# Round_Rev3.net
KiCad netlist of a schematic drawn in EAGLE
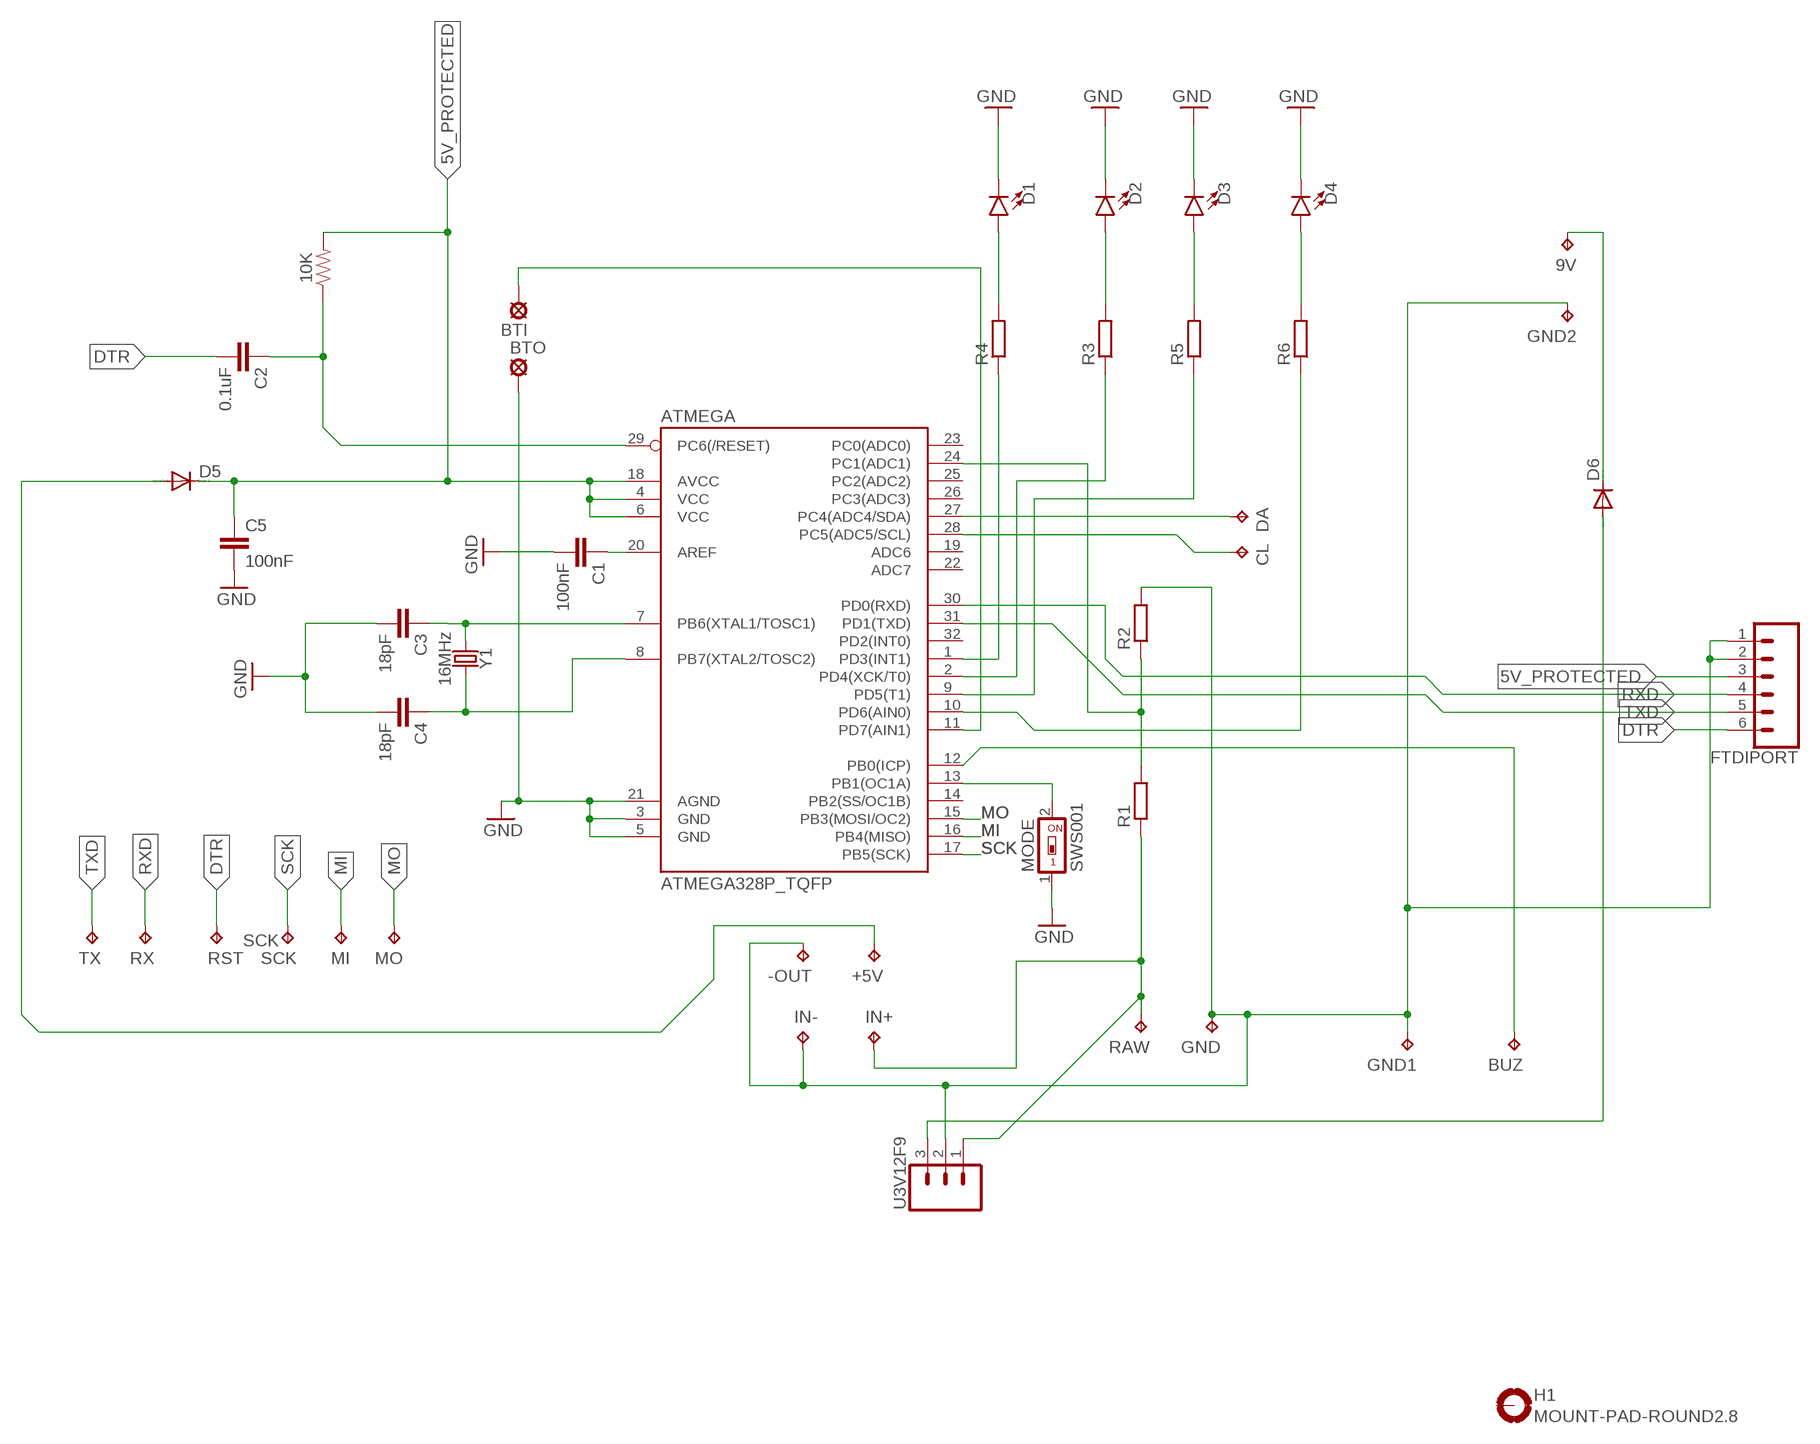
[diagram p0: schematic, sheet 1]

(export (version "E")
  (design (tool "Eeschema 10.0.6"))
  (components
    (comp (ref "+5V")
      (value "TPTP20SQ")
      (footprint "eagle-import:TP20SQ")
      (libsource (lib "eagle-import") (part "TPTP20SQ"))
    )
    (comp (ref "-OUT")
      (value "TPTP20SQ")
      (footprint "eagle-import:TP20SQ")
      (libsource (lib "eagle-import") (part "TPTP20SQ"))
    )
    (comp (ref "9V")
      (value "TPB2,54")
      (footprint "eagle-import:B2,54")
      (libsource (lib "eagle-import") (part "TPB2,54"))
    )
    (comp (ref "10K")
      (value "0.27OHM-0603-1/10W-1%")
      (footprint "eagle-import:0603")
      (libsource (lib "eagle-import") (part "0.27OHM-0603-1/10W-1%"))
    )
    (comp (ref "ATMEGA")
      (value "ATMEGA328P_TQFP")
      (footprint "eagle-import:TQFP32-08")
      (libsource (lib "eagle-import") (part "ATMEGA328P_TQFP"))
    )
    (comp (ref "BTI")
      (value "LSP10")
      (footprint "eagle-import:LSP10")
      (libsource (lib "eagle-import") (part "LSP10"))
    )
    (comp (ref "BTO")
      (value "LSP10")
      (footprint "eagle-import:LSP10")
      (libsource (lib "eagle-import") (part "LSP10"))
    )
    (comp (ref "BUZ")
      (value "TPB2,54")
      (footprint "eagle-import:B2,54")
      (libsource (lib "eagle-import") (part "TPB2,54"))
    )
    (comp (ref "C1")
      (value "100nF")
      (footprint "eagle-import:0603")
      (libsource (lib "eagle-import") (part "10NF-0603-50V-10%"))
    )
    (comp (ref "C2")
      (value "0.1uF")
      (footprint "eagle-import:0603")
      (libsource (lib "eagle-import") (part "10NF-0603-50V-10%"))
    )
    (comp (ref "C3")
      (value "18pF")
      (footprint "eagle-import:0603")
      (libsource (lib "eagle-import") (part "10NF-0603-50V-10%"))
    )
    (comp (ref "C4")
      (value "18pF")
      (footprint "eagle-import:0603")
      (libsource (lib "eagle-import") (part "10NF-0603-50V-10%"))
    )
    (comp (ref "C5")
      (value "100nF")
      (footprint "eagle-import:0603")
      (libsource (lib "eagle-import") (part "10NF-0603-50V-10%"))
    )
    (comp (ref "CL")
      (value "TPB1,27")
      (footprint "eagle-import:B1,27")
      (libsource (lib "eagle-import") (part "TPB1,27"))
    )
    (comp (ref "D1")
      (value "LED1206")
      (footprint "eagle-import:LED-1206")
      (libsource (lib "eagle-import") (part "LED1206"))
    )
    (comp (ref "D2")
      (value "LED1206")
      (footprint "eagle-import:LED-1206")
      (libsource (lib "eagle-import") (part "LED1206"))
    )
    (comp (ref "D3")
      (value "LED1206")
      (footprint "eagle-import:LED-1206")
      (libsource (lib "eagle-import") (part "LED1206"))
    )
    (comp (ref "D4")
      (value "LED1206")
      (footprint "eagle-import:LED-1206")
      (libsource (lib "eagle-import") (part "LED1206"))
    )
    (comp (ref "D5")
      (value "DIODE-SOD106A-R")
      (footprint "eagle-import:SOD106A-R")
      (libsource (lib "eagle-import") (part "DIODE-SOD106A-R"))
    )
    (comp (ref "D6")
      (value "DIODE-SOD106A-R")
      (footprint "eagle-import:SOD106A-R")
      (libsource (lib "eagle-import") (part "DIODE-SOD106A-R"))
    )
    (comp (ref "DA")
      (value "TPB1,27")
      (footprint "eagle-import:B1,27")
      (libsource (lib "eagle-import") (part "TPB1,27"))
    )
    (comp (ref "FTDIPORT")
      (value "CONN_06SMD-1MM")
      (footprint "eagle-import:1X06-1MM")
      (libsource (lib "eagle-import") (part "CONN_06SMD-1MM"))
    )
    (comp (ref "GND")
      (value "TPB2,54")
      (footprint "eagle-import:B2,54")
      (libsource (lib "eagle-import") (part "TPB2,54"))
    )
    (comp (ref "GND1")
      (value "TPB2,54")
      (footprint "eagle-import:B2,54")
      (libsource (lib "eagle-import") (part "TPB2,54"))
    )
    (comp (ref "GND2")
      (value "TPB2,54")
      (footprint "eagle-import:B2,54")
      (libsource (lib "eagle-import") (part "TPB2,54"))
    )
    (comp (ref "H1")
      (value "MOUNT-PAD-ROUND2.8")
      (footprint "eagle-import:2,8-PAD")
      (libsource (lib "eagle-import") (part "MOUNT-PAD-ROUND2.8"))
    )
    (comp (ref "IN+")
      (value "TPTP20SQ")
      (footprint "eagle-import:TP20SQ")
      (libsource (lib "eagle-import") (part "TPTP20SQ"))
    )
    (comp (ref "IN-")
      (value "TPTP20SQ")
      (footprint "eagle-import:TP20SQ")
      (libsource (lib "eagle-import") (part "TPTP20SQ"))
    )
    (comp (ref "MI")
      (value "TPB1,27")
      (footprint "eagle-import:B1,27")
      (libsource (lib "eagle-import") (part "TPB1,27"))
    )
    (comp (ref "MO")
      (value "TPB1,27")
      (footprint "eagle-import:B1,27")
      (libsource (lib "eagle-import") (part "TPB1,27"))
    )
    (comp (ref "MODE")
      (value "SWS001")
      (footprint "eagle-import:SMS-001")
      (libsource (lib "eagle-import") (part "SWS001"))
    )
    (comp (ref "R1")
      (value "R-EU_R1206")
      (footprint "eagle-import:R1206")
      (libsource (lib "eagle-import") (part "R-EU_R1206"))
    )
    (comp (ref "R2")
      (value "R-EU_R1206")
      (footprint "eagle-import:R1206")
      (libsource (lib "eagle-import") (part "R-EU_R1206"))
    )
    (comp (ref "R3")
      (value "R-EU_R1206")
      (footprint "eagle-import:R1206")
      (libsource (lib "eagle-import") (part "R-EU_R1206"))
    )
    (comp (ref "R4")
      (value "R-EU_R1206")
      (footprint "eagle-import:R1206")
      (libsource (lib "eagle-import") (part "R-EU_R1206"))
    )
    (comp (ref "R5")
      (value "R-EU_R1206")
      (footprint "eagle-import:R1206")
      (libsource (lib "eagle-import") (part "R-EU_R1206"))
    )
    (comp (ref "R6")
      (value "R-EU_R1206")
      (footprint "eagle-import:R1206")
      (libsource (lib "eagle-import") (part "R-EU_R1206"))
    )
    (comp (ref "RAW")
      (value "TPB2,54")
      (footprint "eagle-import:B2,54")
      (libsource (lib "eagle-import") (part "TPB2,54"))
    )
    (comp (ref "RST")
      (value "TPB1,27")
      (footprint "eagle-import:B1,27")
      (libsource (lib "eagle-import") (part "TPB1,27"))
    )
    (comp (ref "RX")
      (value "TPB1,27")
      (footprint "eagle-import:B1,27")
      (libsource (lib "eagle-import") (part "TPB1,27"))
    )
    (comp (ref "SCK")
      (value "TPB1,27")
      (footprint "eagle-import:B1,27")
      (fields (field (name "TP_SIGNAL_NAME") "SCK"))
      (libsource (lib "eagle-import") (part "TPB1,27"))
    )
    (comp (ref "TX")
      (value "TPB1,27")
      (footprint "eagle-import:B1,27")
      (libsource (lib "eagle-import") (part "TPB1,27"))
    )
    (comp (ref "U3V12F9")
      (value "CONN_03")
      (footprint "eagle-import:1X03")
      (libsource (lib "eagle-import") (part "CONN_03"))
    )
    (comp (ref "Y1")
      (value "16MHz")
      (footprint "eagle-import:CRYSTAL-SMD-5X3.2-2PAD")
      (libsource (lib "eagle-import") (part "CRYSTALSMD-5X3.2-2PAD"))
    )
  )
  (nets
    (net (code "1") (name "5V_PROTECTED") (class "Default")
      (node (ref "10K") (pin "2") (pinfunction "2_2") (pintype "passive"))
      (node (ref "ATMEGA") (pin "18") (pinfunction "AVCC_18") (pintype "bidirectional"))
      (node (ref "ATMEGA") (pin "4") (pinfunction "VCC_4") (pintype "bidirectional"))
      (node (ref "ATMEGA") (pin "6") (pinfunction "VCC_6") (pintype "bidirectional"))
      (node (ref "C5") (pin "1") (pinfunction "1_1") (pintype "passive"))
      (node (ref "D5") (pin "C") (pinfunction "C_C") (pintype "passive"))
      (node (ref "FTDIPORT") (pin "3") (pinfunction "3_3") (pintype "passive"))
    )
    (net (code "2") (name "DTR") (class "Default")
      (node (ref "C2") (pin "2") (pinfunction "2_2") (pintype "passive"))
      (node (ref "FTDIPORT") (pin "6") (pinfunction "6_6") (pintype "passive"))
      (node (ref "RST") (pin "TP") (pinfunction "TP_TP") (pintype "input"))
    )
    (net (code "3") (name "GND") (class "Default")
      (node (ref "-OUT") (pin "TP") (pinfunction "TP_TP") (pintype "input"))
      (node (ref "ATMEGA") (pin "21") (pinfunction "AGND_21") (pintype "bidirectional"))
      (node (ref "ATMEGA") (pin "3") (pinfunction "GND_3") (pintype "bidirectional"))
      (node (ref "ATMEGA") (pin "5") (pinfunction "GND_5") (pintype "bidirectional"))
      (node (ref "BTO") (pin "MP") (pinfunction "MP_MP") (pintype "passive"))
      (node (ref "C1") (pin "2") (pinfunction "2_2") (pintype "passive"))
      (node (ref "C3") (pin "2") (pinfunction "2_2") (pintype "passive"))
      (node (ref "C4") (pin "2") (pinfunction "2_2") (pintype "passive"))
      (node (ref "C5") (pin "2") (pinfunction "2_2") (pintype "passive"))
      (node (ref "D1") (pin "C") (pinfunction "C_C") (pintype "passive"))
      (node (ref "D2") (pin "C") (pinfunction "C_C") (pintype "passive"))
      (node (ref "D3") (pin "C") (pinfunction "C_C") (pintype "passive"))
      (node (ref "D4") (pin "C") (pinfunction "C_C") (pintype "passive"))
      (node (ref "FTDIPORT") (pin "1") (pinfunction "1_1") (pintype "passive"))
      (node (ref "FTDIPORT") (pin "2") (pinfunction "2_2") (pintype "passive"))
      (node (ref "GND") (pin "TP") (pinfunction "TP_TP") (pintype "input"))
      (node (ref "GND1") (pin "TP") (pinfunction "TP_TP") (pintype "input"))
      (node (ref "GND2") (pin "TP") (pinfunction "TP_TP") (pintype "input"))
      (node (ref "IN-") (pin "TP") (pinfunction "TP_TP") (pintype "input"))
      (node (ref "MODE") (pin "1") (pinfunction "1_1") (pintype "passive"))
      (node (ref "R2") (pin "2") (pinfunction "2_2") (pintype "passive"))
      (node (ref "U3V12F9") (pin "2") (pinfunction "2_2") (pintype "passive"))
    )
    (net (code "4") (name "MI") (class "Default")
      (node (ref "ATMEGA") (pin "16") (pinfunction "PB4(MISO)_16") (pintype "bidirectional"))
      (node (ref "MI") (pin "TP") (pinfunction "TP_TP") (pintype "input"))
    )
    (net (code "5") (name "MO") (class "Default")
      (node (ref "ATMEGA") (pin "15") (pinfunction "PB3(MOSI/OC2)_15") (pintype "bidirectional"))
      (node (ref "MO") (pin "TP") (pinfunction "TP_TP") (pintype "input"))
    )
    (net (code "6") (name "Net-(+5V-PadTP)") (class "Default")
      (node (ref "+5V") (pin "TP") (pinfunction "TP_TP") (pintype "input"))
      (node (ref "D5") (pin "A") (pinfunction "A_A") (pintype "passive"))
    )
    (net (code "7") (name "Net-(9V-PadTP)") (class "Default")
      (node (ref "9V") (pin "TP") (pinfunction "TP_TP") (pintype "input"))
      (node (ref "D6") (pin "C") (pinfunction "C_C") (pintype "passive"))
    )
    (net (code "8") (name "Net-(ATMEGA-AREF)") (class "Default")
      (node (ref "ATMEGA") (pin "20") (pinfunction "AREF_20") (pintype "bidirectional"))
      (node (ref "C1") (pin "1") (pinfunction "1_1") (pintype "passive"))
    )
    (net (code "9") (name "Net-(ATMEGA-PB0(ICP))") (class "Default")
      (node (ref "ATMEGA") (pin "12") (pinfunction "PB0(ICP)_12") (pintype "bidirectional"))
      (node (ref "BUZ") (pin "TP") (pinfunction "TP_TP") (pintype "input"))
    )
    (net (code "10") (name "Net-(ATMEGA-PB1(OC1A))") (class "Default")
      (node (ref "ATMEGA") (pin "13") (pinfunction "PB1(OC1A)_13") (pintype "bidirectional"))
      (node (ref "MODE") (pin "2") (pinfunction "2_2") (pintype "passive"))
    )
    (net (code "11") (name "Net-(ATMEGA-PB6(XTAL1{slash}TOSC1))") (class "Default")
      (node (ref "ATMEGA") (pin "7") (pinfunction "PB6(XTAL1/TOSC1)_7") (pintype "bidirectional"))
      (node (ref "C3") (pin "1") (pinfunction "1_1") (pintype "passive"))
      (node (ref "Y1") (pin "P$1") (pinfunction "1_P$1") (pintype "passive"))
    )
    (net (code "12") (name "Net-(ATMEGA-PB7(XTAL2{slash}TOSC2))") (class "Default")
      (node (ref "ATMEGA") (pin "8") (pinfunction "PB7(XTAL2/TOSC2)_8") (pintype "bidirectional"))
      (node (ref "C4") (pin "1") (pinfunction "1_1") (pintype "passive"))
      (node (ref "Y1") (pin "P$2") (pinfunction "2_P$2") (pintype "passive"))
    )
    (net (code "13") (name "Net-(ATMEGA-PC1(ADC1))") (class "Default")
      (node (ref "ATMEGA") (pin "24") (pinfunction "PC1(ADC1)_24") (pintype "bidirectional"))
      (node (ref "R1") (pin "2") (pinfunction "2_2") (pintype "passive"))
      (node (ref "R2") (pin "1") (pinfunction "1_1") (pintype "passive"))
    )
    (net (code "14") (name "Net-(ATMEGA-PC4(ADC4{slash}SDA))") (class "Default")
      (node (ref "ATMEGA") (pin "27") (pinfunction "PC4(ADC4/SDA)_27") (pintype "bidirectional"))
      (node (ref "DA") (pin "TP") (pinfunction "TP_TP") (pintype "input"))
    )
    (net (code "15") (name "Net-(ATMEGA-PC5(ADC5{slash}SCL))") (class "Default")
      (node (ref "ATMEGA") (pin "28") (pinfunction "PC5(ADC5/SCL)_28") (pintype "bidirectional"))
      (node (ref "CL") (pin "TP") (pinfunction "TP_TP") (pintype "input"))
    )
    (net (code "16") (name "Net-(ATMEGA-PC6({slash}RESET))") (class "Default")
      (node (ref "10K") (pin "1") (pinfunction "1_1") (pintype "passive"))
      (node (ref "ATMEGA") (pin "29") (pinfunction "PC6(/RESET)_29") (pintype "bidirectional"))
      (node (ref "C2") (pin "1") (pinfunction "1_1") (pintype "passive"))
    )
    (net (code "17") (name "Net-(ATMEGA-PD3(INT1))") (class "Default")
      (node (ref "ATMEGA") (pin "1") (pinfunction "PD3(INT1)_1") (pintype "bidirectional"))
      (node (ref "R4") (pin "1") (pinfunction "1_1") (pintype "passive"))
    )
    (net (code "18") (name "Net-(ATMEGA-PD4(XCK{slash}T0))") (class "Default")
      (node (ref "ATMEGA") (pin "2") (pinfunction "PD4(XCK/T0)_2") (pintype "bidirectional"))
      (node (ref "R3") (pin "1") (pinfunction "1_1") (pintype "passive"))
    )
    (net (code "19") (name "Net-(ATMEGA-PD5(T1))") (class "Default")
      (node (ref "ATMEGA") (pin "9") (pinfunction "PD5(T1)_9") (pintype "bidirectional"))
      (node (ref "R5") (pin "1") (pinfunction "1_1") (pintype "passive"))
    )
    (net (code "20") (name "Net-(ATMEGA-PD6(AIN0))") (class "Default")
      (node (ref "ATMEGA") (pin "10") (pinfunction "PD6(AIN0)_10") (pintype "bidirectional"))
      (node (ref "R6") (pin "1") (pinfunction "1_1") (pintype "passive"))
    )
    (net (code "21") (name "Net-(ATMEGA-PD7(AIN1))") (class "Default")
      (node (ref "ATMEGA") (pin "11") (pinfunction "PD7(AIN1)_11") (pintype "bidirectional"))
      (node (ref "BTI") (pin "MP") (pinfunction "MP_MP") (pintype "passive"))
    )
    (net (code "22") (name "Net-(D1-PadA)") (class "Default")
      (node (ref "D1") (pin "A") (pinfunction "A_A") (pintype "passive"))
      (node (ref "R4") (pin "2") (pinfunction "2_2") (pintype "passive"))
    )
    (net (code "23") (name "Net-(D2-PadA)") (class "Default")
      (node (ref "D2") (pin "A") (pinfunction "A_A") (pintype "passive"))
      (node (ref "R3") (pin "2") (pinfunction "2_2") (pintype "passive"))
    )
    (net (code "24") (name "Net-(D3-PadA)") (class "Default")
      (node (ref "D3") (pin "A") (pinfunction "A_A") (pintype "passive"))
      (node (ref "R5") (pin "2") (pinfunction "2_2") (pintype "passive"))
    )
    (net (code "25") (name "Net-(D4-PadA)") (class "Default")
      (node (ref "D4") (pin "A") (pinfunction "A_A") (pintype "passive"))
      (node (ref "R6") (pin "2") (pinfunction "2_2") (pintype "passive"))
    )
    (net (code "26") (name "Net-(D6-PadA)") (class "Default")
      (node (ref "D6") (pin "A") (pinfunction "A_A") (pintype "passive"))
      (node (ref "U3V12F9") (pin "3") (pinfunction "3_3") (pintype "passive"))
    )
    (net (code "27") (name "Net-(IN+-PadTP)") (class "Default")
      (node (ref "IN+") (pin "TP") (pinfunction "TP_TP") (pintype "input"))
      (node (ref "R1") (pin "1") (pinfunction "1_1") (pintype "passive"))
      (node (ref "RAW") (pin "TP") (pinfunction "TP_TP") (pintype "input"))
      (node (ref "U3V12F9") (pin "1") (pinfunction "1_1") (pintype "passive"))
    )
    (net (code "28") (name "RXD") (class "Default")
      (node (ref "ATMEGA") (pin "30") (pinfunction "PD0(RXD)_30") (pintype "bidirectional"))
      (node (ref "FTDIPORT") (pin "4") (pinfunction "4_4") (pintype "passive"))
      (node (ref "RX") (pin "TP") (pinfunction "TP_TP") (pintype "input"))
    )
    (net (code "29") (name "SCK") (class "Default")
      (node (ref "ATMEGA") (pin "17") (pinfunction "PB5(SCK)_17") (pintype "bidirectional"))
      (node (ref "SCK") (pin "TP") (pinfunction "TP_TP") (pintype "input"))
    )
    (net (code "30") (name "TXD") (class "Default")
      (node (ref "ATMEGA") (pin "31") (pinfunction "PD1(TXD)_31") (pintype "bidirectional"))
      (node (ref "FTDIPORT") (pin "5") (pinfunction "5_5") (pintype "passive"))
      (node (ref "TX") (pin "TP") (pinfunction "TP_TP") (pintype "input"))
    )
    (net (code "31") (name "unconnected-(ATMEGA-ADC6-Pad19)") (class "Default")
      (node (ref "ATMEGA") (pin "19") (pinfunction "ADC6_19") (pintype "bidirectional"))
    )
    (net (code "32") (name "unconnected-(ATMEGA-ADC7-Pad22)") (class "Default")
      (node (ref "ATMEGA") (pin "22") (pinfunction "ADC7_22") (pintype "bidirectional"))
    )
    (net (code "33") (name "unconnected-(ATMEGA-PB2(SS{slash}OC1B)-Pad14)") (class "Default")
      (node (ref "ATMEGA") (pin "14") (pinfunction "PB2(SS/OC1B)_14") (pintype "bidirectional"))
    )
    (net (code "34") (name "unconnected-(ATMEGA-PC0(ADC0)-Pad23)") (class "Default")
      (node (ref "ATMEGA") (pin "23") (pinfunction "PC0(ADC0)_23") (pintype "bidirectional"))
    )
    (net (code "35") (name "unconnected-(ATMEGA-PC2(ADC2)-Pad25)") (class "Default")
      (node (ref "ATMEGA") (pin "25") (pinfunction "PC2(ADC2)_25") (pintype "bidirectional"))
    )
    (net (code "36") (name "unconnected-(ATMEGA-PC3(ADC3)-Pad26)") (class "Default")
      (node (ref "ATMEGA") (pin "26") (pinfunction "PC3(ADC3)_26") (pintype "bidirectional"))
    )
    (net (code "37") (name "unconnected-(ATMEGA-PD2(INT0)-Pad32)") (class "Default")
      (node (ref "ATMEGA") (pin "32") (pinfunction "PD2(INT0)_32") (pintype "bidirectional"))
    )
    (net (code "38") (name "unconnected-(H1-MOUNT-PadB2,8)") (class "Default")
      (node (ref "H1") (pin "B2,8") (pinfunction "MOUNT_B2,8") (pintype "passive"))
    )
  )
)
